# uZed_breakout.net
KiCad netlist of a schematic drawn in Altium Designer
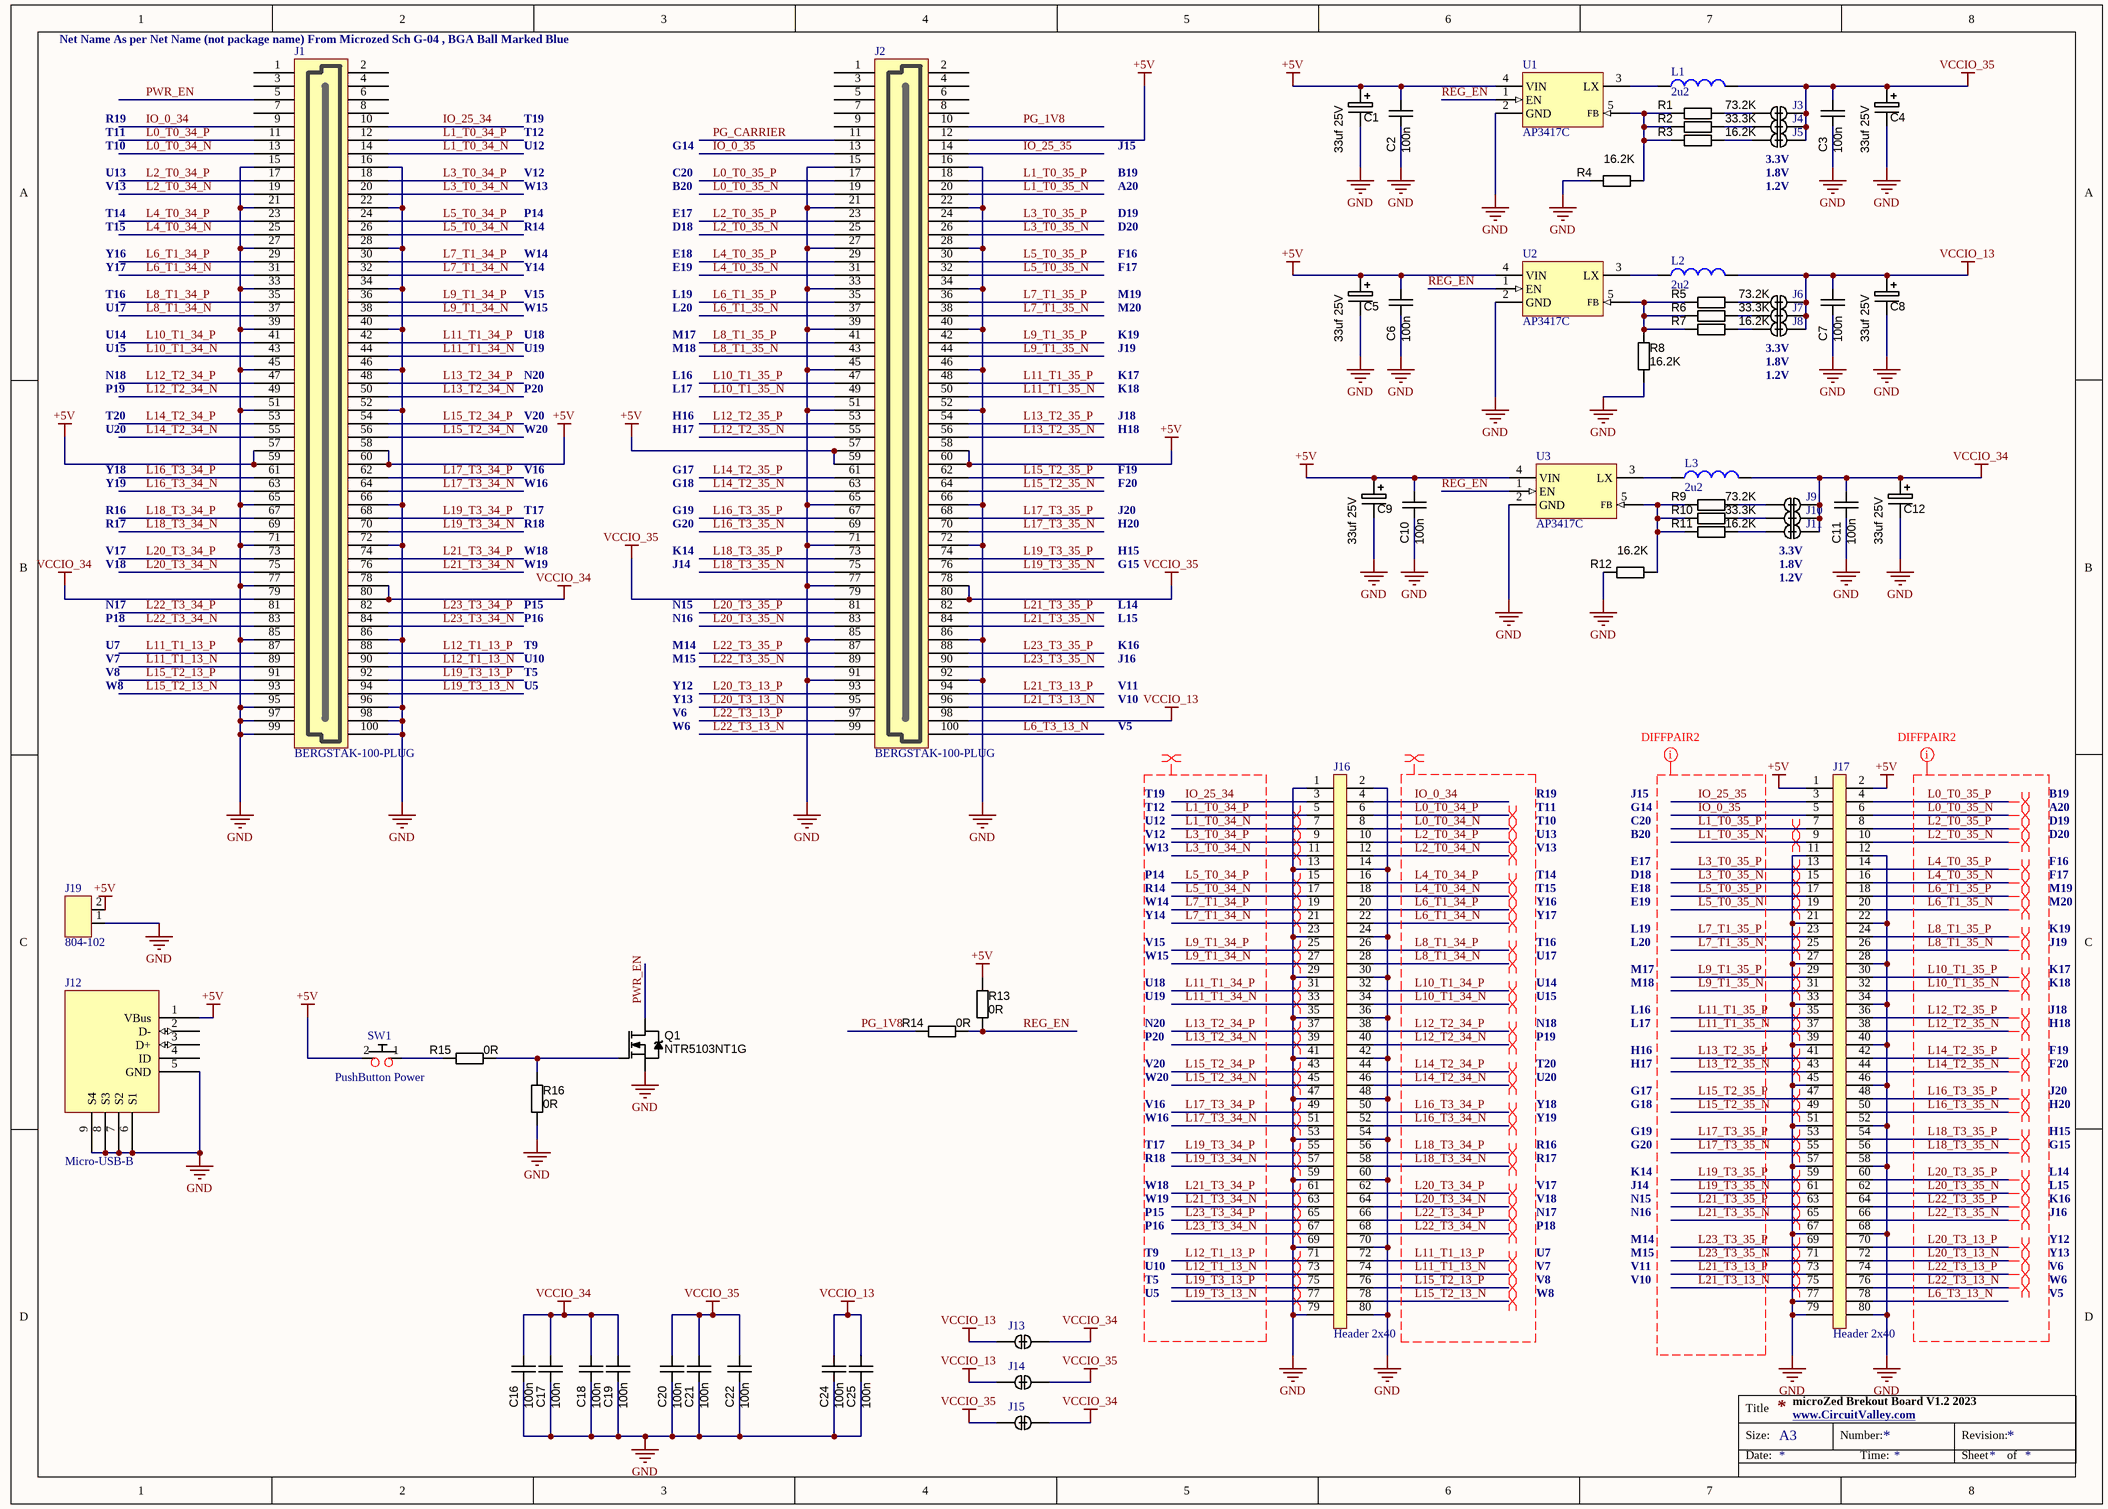
[diagram p0: uZed_breakout.SchDoc]

(export (version "E")
  (design (tool "Eeschema 10.0.6"))
  (components
    (comp (ref "C1")
      (value "33uf 25V")
      (footprint "CAPMP7343X310N")
      (description "Capacitor SMD Tant 330uF 20% 6V3 2917")
      (fields
        (field (name "TOLERANCE") "±20%")
        (field (name "MANUFACTURER PART NUMBER") "T520D337M006ATE015")
      )
      (libsource (lib "PBL - Capacitors") (part "CAPT_330u_2917_6V3"))
    )
    (comp (ref "C2")
      (value "100n")
      (footprint "CAPC1608N")
      (description "Capacitor SMD Cer 10pF 5% 50V NP0 0603")
      (fields (field (name "TOLERANCE") "±5%") (field (name "PART") "C0603X104K5RAC"))
      (libsource (lib "PBL - Capacitors") (part "CAPC_10p_0603_NP0_1%_50V"))
    )
    (comp (ref "C3")
      (value "100n")
      (footprint "CAPC1608N")
      (description "Capacitor SMD Cer 10pF 5% 50V NP0 0603")
      (fields (field (name "TOLERANCE") "±5%") (field (name "PART") "C0603X104K5RAC"))
      (libsource (lib "PBL - Capacitors") (part "CAPC_10p_0603_NP0_1%_50V"))
    )
    (comp (ref "C4")
      (value "33uf 25V")
      (footprint "CAPMP7343X310N")
      (description "Capacitor SMD Tant 330uF 20% 6V3 2917")
      (fields
        (field (name "TOLERANCE") "±20%")
        (field (name "MANUFACTURER PART NUMBER") "T520D337M006ATE015")
      )
      (libsource (lib "PBL - Capacitors") (part "CAPT_330u_2917_6V3"))
    )
    (comp (ref "C5")
      (value "33uf 25V")
      (footprint "CAPMP7343X310N")
      (description "Capacitor SMD Tant 330uF 20% 6V3 2917")
      (fields
        (field (name "TOLERANCE") "±20%")
        (field (name "MANUFACTURER PART NUMBER") "T520D337M006ATE015")
      )
      (libsource (lib "PBL - Capacitors") (part "CAPT_330u_2917_6V3"))
    )
    (comp (ref "C6")
      (value "100n")
      (footprint "CAPC1608N")
      (description "Capacitor SMD Cer 10pF 5% 50V NP0 0603")
      (fields (field (name "TOLERANCE") "±5%") (field (name "PART") "C0603X104K5RAC"))
      (libsource (lib "PBL - Capacitors") (part "CAPC_10p_0603_NP0_1%_50V"))
    )
    (comp (ref "C7")
      (value "100n")
      (footprint "CAPC1608N")
      (description "Capacitor SMD Cer 10pF 5% 50V NP0 0603")
      (fields (field (name "TOLERANCE") "±5%") (field (name "PART") "C0603X104K5RAC"))
      (libsource (lib "PBL - Capacitors") (part "CAPC_10p_0603_NP0_1%_50V"))
    )
    (comp (ref "C8")
      (value "33uf 25V")
      (footprint "CAPMP7343X310N")
      (description "Capacitor SMD Tant 330uF 20% 6V3 2917")
      (fields
        (field (name "TOLERANCE") "±20%")
        (field (name "MANUFACTURER PART NUMBER") "T520D337M006ATE015")
      )
      (libsource (lib "PBL - Capacitors") (part "CAPT_330u_2917_6V3"))
    )
    (comp (ref "C9")
      (value "33uf 25V")
      (footprint "CAPMP7343X310N")
      (description "Capacitor SMD Tant 330uF 20% 6V3 2917")
      (fields
        (field (name "TOLERANCE") "±20%")
        (field (name "MANUFACTURER PART NUMBER") "T520D337M006ATE015")
      )
      (libsource (lib "PBL - Capacitors") (part "CAPT_330u_2917_6V3"))
    )
    (comp (ref "C10")
      (value "100n")
      (footprint "CAPC1608N")
      (description "Capacitor SMD Cer 10pF 5% 50V NP0 0603")
      (fields (field (name "TOLERANCE") "±5%") (field (name "PART") "C0603X104K5RAC"))
      (libsource (lib "PBL - Capacitors") (part "CAPC_10p_0603_NP0_1%_50V"))
    )
    (comp (ref "C11")
      (value "100n")
      (footprint "CAPC1608N")
      (description "Capacitor SMD Cer 10pF 5% 50V NP0 0603")
      (fields (field (name "TOLERANCE") "±5%") (field (name "PART") "C0603X104K5RAC"))
      (libsource (lib "PBL - Capacitors") (part "CAPC_10p_0603_NP0_1%_50V"))
    )
    (comp (ref "C12")
      (value "33uf 25V")
      (footprint "CAPMP7343X310N")
      (description "Capacitor SMD Tant 330uF 20% 6V3 2917")
      (fields
        (field (name "TOLERANCE") "±20%")
        (field (name "MANUFACTURER PART NUMBER") "T520D337M006ATE015")
      )
      (libsource (lib "PBL - Capacitors") (part "CAPT_330u_2917_6V3"))
    )
    (comp (ref "C16")
      (value "100n")
      (footprint "CAPC1608N")
      (description "Capacitor SMD Cer 10pF 5% 50V NP0 0603")
      (fields (field (name "TOLERANCE") "±5%") (field (name "PART") "C0603X104K5RAC"))
      (libsource (lib "PBL - Capacitors") (part "CAPC_10p_0603_NP0_1%_50V"))
    )
    (comp (ref "C17")
      (value "100n")
      (footprint "CAPC1608N")
      (description "Capacitor SMD Cer 10pF 5% 50V NP0 0603")
      (fields (field (name "TOLERANCE") "±5%") (field (name "PART") "C0603X104K5RAC"))
      (libsource (lib "PBL - Capacitors") (part "CAPC_10p_0603_NP0_1%_50V"))
    )
    (comp (ref "C18")
      (value "100n")
      (footprint "CAPC1608N")
      (description "Capacitor SMD Cer 10pF 5% 50V NP0 0603")
      (fields (field (name "TOLERANCE") "±5%") (field (name "PART") "C0603X104K5RAC"))
      (libsource (lib "PBL - Capacitors") (part "CAPC_10p_0603_NP0_1%_50V"))
    )
    (comp (ref "C19")
      (value "100n")
      (footprint "CAPC1608N")
      (description "Capacitor SMD Cer 10pF 5% 50V NP0 0603")
      (fields (field (name "TOLERANCE") "±5%") (field (name "PART") "C0603X104K5RAC"))
      (libsource (lib "PBL - Capacitors") (part "CAPC_10p_0603_NP0_1%_50V"))
    )
    (comp (ref "C20")
      (value "100n")
      (footprint "CAPC1608N")
      (description "Capacitor SMD Cer 10pF 5% 50V NP0 0603")
      (fields (field (name "TOLERANCE") "±5%") (field (name "PART") "C0603X104K5RAC"))
      (libsource (lib "PBL - Capacitors") (part "CAPC_10p_0603_NP0_1%_50V"))
    )
    (comp (ref "C21")
      (value "100n")
      (footprint "CAPC1608N")
      (description "Capacitor SMD Cer 10pF 5% 50V NP0 0603")
      (fields (field (name "TOLERANCE") "±5%") (field (name "PART") "C0603X104K5RAC"))
      (libsource (lib "PBL - Capacitors") (part "CAPC_10p_0603_NP0_1%_50V"))
    )
    (comp (ref "C22")
      (value "100n")
      (footprint "CAPC1608N")
      (description "Capacitor SMD Cer 10pF 5% 50V NP0 0603")
      (fields (field (name "TOLERANCE") "±5%") (field (name "PART") "C0603X104K5RAC"))
      (libsource (lib "PBL - Capacitors") (part "CAPC_10p_0603_NP0_1%_50V"))
    )
    (comp (ref "C24")
      (value "100n")
      (footprint "CAPC1608N")
      (description "Capacitor SMD Cer 10pF 5% 50V NP0 0603")
      (fields (field (name "TOLERANCE") "±5%") (field (name "PART") "C0603X104K5RAC"))
      (libsource (lib "PBL - Capacitors") (part "CAPC_10p_0603_NP0_1%_50V"))
    )
    (comp (ref "C25")
      (value "100n")
      (footprint "CAPC1608N")
      (description "Capacitor SMD Cer 10pF 5% 50V NP0 0603")
      (fields (field (name "TOLERANCE") "±5%") (field (name "PART") "C0603X104K5RAC"))
      (libsource (lib "PBL - Capacitors") (part "CAPC_10p_0603_NP0_1%_50V"))
    )
    (comp (ref "J1")
      (value "BERGSTAK-100-PLUG")
      (footprint "61083-101400LF")
      (libsource (lib "cvlib") (part "BERGSTAK-100-PLUG"))
    )
    (comp (ref "J2")
      (value "BERGSTAK-100-PLUG")
      (footprint "61083-101400LF")
      (libsource (lib "cvlib") (part "BERGSTAK-100-PLUG"))
    )
    (comp (ref "J3")
      (value "~")
      (footprint "BYPASS-CLOSED")
      (description "SOLDERDOT BYPASS")
      (libsource (lib "Generic") (part "BYPASS-CLOSED"))
    )
    (comp (ref "J4")
      (value "~")
      (footprint "BYPASS-CLOSED")
      (description "SOLDERDOT BYPASS")
      (libsource (lib "Generic") (part "BYPASS-CLOSED"))
    )
    (comp (ref "J5")
      (value "~")
      (footprint "BYPASS-CLOSED")
      (description "SOLDERDOT BYPASS")
      (libsource (lib "Generic") (part "BYPASS-CLOSED"))
    )
    (comp (ref "J6")
      (value "~")
      (footprint "BYPASS-CLOSED")
      (description "SOLDERDOT BYPASS")
      (libsource (lib "Generic") (part "BYPASS-CLOSED"))
    )
    (comp (ref "J7")
      (value "~")
      (footprint "BYPASS-CLOSED")
      (description "SOLDERDOT BYPASS")
      (libsource (lib "Generic") (part "BYPASS-CLOSED"))
    )
    (comp (ref "J8")
      (value "~")
      (footprint "BYPASS-CLOSED")
      (description "SOLDERDOT BYPASS")
      (libsource (lib "Generic") (part "BYPASS-CLOSED"))
    )
    (comp (ref "J9")
      (value "~")
      (footprint "BYPASS-CLOSED")
      (description "SOLDERDOT BYPASS")
      (libsource (lib "Generic") (part "BYPASS-CLOSED"))
    )
    (comp (ref "J10")
      (value "~")
      (footprint "BYPASS-CLOSED")
      (description "SOLDERDOT BYPASS")
      (libsource (lib "Generic") (part "BYPASS-CLOSED"))
    )
    (comp (ref "J11")
      (value "~")
      (footprint "BYPASS-CLOSED")
      (description "SOLDERDOT BYPASS")
      (libsource (lib "Generic") (part "BYPASS-CLOSED"))
    )
    (comp (ref "J12")
      (value "Micro-USB-B")
      (footprint "10118193-0001lfc")
      (fields (field (name "PART") "10118193-0001lfc"))
      (libsource (lib "USB-MICROB-HW-MC-5F") (part "Micro-USB-B"))
    )
    (comp (ref "J13")
      (value "~")
      (footprint "BYPASS-CLOSED")
      (description "SOLDERDOT BYPASS")
      (libsource (lib "Generic") (part "BYPASS-CLOSED"))
    )
    (comp (ref "J14")
      (value "~")
      (footprint "BYPASS-CLOSED")
      (description "SOLDERDOT BYPASS")
      (libsource (lib "Generic") (part "BYPASS-CLOSED"))
    )
    (comp (ref "J15")
      (value "~")
      (footprint "BYPASS-CLOSED")
      (description "SOLDERDOT BYPASS")
      (libsource (lib "Generic") (part "BYPASS-CLOSED"))
    )
    (comp (ref "J16")
      (value "Header 2x40")
      (footprint "Header_2x40")
      (libsource (lib "cvlib") (part "Header_2x40"))
    )
    (comp (ref "J17")
      (value "Header 2x40")
      (footprint "Header_2x40")
      (libsource (lib "cvlib") (part "Header_2x40"))
    )
    (comp (ref "J19") (value "804-102") (footprint "804-102") (libsource (lib "cvlib") (part "804-102")))
    (comp (ref "L1")
      (value "2u2")
      (footprint "TAIYO_NRS4018T2R2MDGJ")
      (fields (field (name "PARTNUMBER") "NRS4018T2R2MDGJ"))
      (libsource (lib "Inductor") (part "inductor_smd"))
    )
    (comp (ref "L2")
      (value "2u2")
      (footprint "TAIYO_NRS4018T2R2MDGJ")
      (fields (field (name "PARTNUMBER") "NRS4018T2R2MDGJ"))
      (libsource (lib "Inductor") (part "inductor_smd"))
    )
    (comp (ref "L3")
      (value "2u2")
      (footprint "TAIYO_NRS4018T2R2MDGJ")
      (fields (field (name "PARTNUMBER") "NRS4018T2R2MDGJ"))
      (libsource (lib "Inductor") (part "inductor_smd"))
    )
    (comp (ref "Q1")
      (value "NTR5103NT1G")
      (footprint "SOT23-3")
      (description "MOSFET SMD N-CH 100V 170mA SOT23-3")
      (libsource (lib "PBL - Transistors") (part "MOSFET_BSS123"))
    )
    (comp (ref "R1")
      (value "73.2K")
      (footprint "RESC1608N_ZERO")
      (description "Resistor SMD chip 0.0 Ohm 0.1W 0603")
      (fields (field (name "TOLERANCE") "±5%") (field (name "Comment") "Thick Film"))
      (libsource (lib "PBL - Resistors") (part "RES_0R_0603"))
    )
    (comp (ref "R2")
      (value "33.3K")
      (footprint "RESC1608N_ZERO")
      (description "Resistor SMD chip 0.0 Ohm 0.1W 0603")
      (fields (field (name "TOLERANCE") "±5%") (field (name "Comment") "Thick Film"))
      (libsource (lib "PBL - Resistors") (part "RES_0R_0603"))
    )
    (comp (ref "R3")
      (value "16.2K")
      (footprint "RESC1608N_ZERO")
      (description "Resistor SMD chip 0.0 Ohm 0.1W 0603")
      (fields (field (name "TOLERANCE") "±5%") (field (name "Comment") "Thick Film"))
      (libsource (lib "PBL - Resistors") (part "RES_0R_0603"))
    )
    (comp (ref "R4")
      (value "16.2K")
      (footprint "RESC1608N_ZERO")
      (description "Resistor SMD chip 0.0 Ohm 0.1W 0603")
      (fields (field (name "TOLERANCE") "±5%") (field (name "Comment") "Thick Film"))
      (libsource (lib "PBL - Resistors") (part "RES_0R_0603"))
    )
    (comp (ref "R5")
      (value "73.2K")
      (footprint "RESC1608N_ZERO")
      (description "Resistor SMD chip 0.0 Ohm 0.1W 0603")
      (fields (field (name "TOLERANCE") "±5%") (field (name "Comment") "Thick Film"))
      (libsource (lib "") (part "RES_0R_0603_2"))
    )
    (comp (ref "R6")
      (value "33.3K")
      (footprint "RESC1608N_ZERO")
      (description "Resistor SMD chip 0.0 Ohm 0.1W 0603")
      (fields (field (name "TOLERANCE") "±5%") (field (name "Comment") "Thick Film"))
      (libsource (lib "") (part "RES_0R_0603_2"))
    )
    (comp (ref "R7")
      (value "16.2K")
      (footprint "RESC1608N_ZERO")
      (description "Resistor SMD chip 0.0 Ohm 0.1W 0603")
      (fields (field (name "TOLERANCE") "±5%") (field (name "Comment") "Thick Film"))
      (libsource (lib "") (part "RES_0R_0603_2"))
    )
    (comp (ref "R8")
      (value "16.2K")
      (footprint "RESC1608N_ZERO")
      (description "Resistor SMD chip 0.0 Ohm 0.1W 0603")
      (fields (field (name "TOLERANCE") "±5%") (field (name "Comment") "Thick Film"))
      (libsource (lib "") (part "RES_0R_0603_3"))
    )
    (comp (ref "R9")
      (value "73.2K")
      (footprint "RESC1608N_ZERO")
      (description "Resistor SMD chip 0.0 Ohm 0.1W 0603")
      (fields (field (name "TOLERANCE") "±5%") (field (name "Comment") "Thick Film"))
      (libsource (lib "PBL - Resistors") (part "RES_0R_0603"))
    )
    (comp (ref "R10")
      (value "33.3K")
      (footprint "RESC1608N_ZERO")
      (description "Resistor SMD chip 0.0 Ohm 0.1W 0603")
      (fields (field (name "TOLERANCE") "±5%") (field (name "Comment") "Thick Film"))
      (libsource (lib "PBL - Resistors") (part "RES_0R_0603"))
    )
    (comp (ref "R11")
      (value "16.2K")
      (footprint "RESC1608N_ZERO")
      (description "Resistor SMD chip 0.0 Ohm 0.1W 0603")
      (fields (field (name "TOLERANCE") "±5%") (field (name "Comment") "Thick Film"))
      (libsource (lib "PBL - Resistors") (part "RES_0R_0603"))
    )
    (comp (ref "R12")
      (value "16.2K")
      (footprint "RESC1608N_ZERO")
      (description "Resistor SMD chip 0.0 Ohm 0.1W 0603")
      (fields (field (name "TOLERANCE") "±5%") (field (name "Comment") "Thick Film"))
      (libsource (lib "PBL - Resistors") (part "RES_0R_0603"))
    )
    (comp (ref "R13")
      (value "0R")
      (footprint "RESC1608N_ZERO")
      (description "Resistor SMD chip 0.0 Ohm 0.1W 0603")
      (fields (field (name "TOLERANCE") "±5%") (field (name "Comment") "Thick Film"))
      (libsource (lib "") (part "RES_0R_0603_1"))
    )
    (comp (ref "R14")
      (value "0R")
      (footprint "RESC1608N_ZERO")
      (description "Resistor SMD chip 0.0 Ohm 0.1W 0603")
      (fields (field (name "TOLERANCE") "±5%") (field (name "Comment") "Thick Film"))
      (libsource (lib "PBL - Resistors") (part "RES_0R_0603"))
    )
    (comp (ref "R15")
      (value "0R")
      (footprint "RESC1608N_ZERO")
      (description "Resistor SMD chip 0.0 Ohm 0.1W 0603")
      (fields (field (name "TOLERANCE") "±5%") (field (name "Comment") "Thick Film"))
      (libsource (lib "PBL - Resistors") (part "RES_0R_0603"))
    )
    (comp (ref "R16")
      (value "0R")
      (footprint "RESC1608N_ZERO")
      (description "Resistor SMD chip 0.0 Ohm 0.1W 0603")
      (fields (field (name "TOLERANCE") "±5%") (field (name "Comment") "Thick Film"))
      (libsource (lib "") (part "RES_0R_0603_1"))
    )
    (comp (ref "SW1")
      (value "PushButton Power")
      (footprint "PushButtonGrid5.08x3.81")
      (libsource (lib "PushSwitchSmall") (part "PushButton"))
    )
    (comp (ref "U1") (value "AP3417C") (footprint "SOT23-5") (libsource (lib "cvlib") (part "AP3417C")))
    (comp (ref "U2") (value "AP3417C") (footprint "SOT23-5") (libsource (lib "cvlib") (part "AP3417C")))
    (comp (ref "U3") (value "AP3417C") (footprint "SOT23-5") (libsource (lib "cvlib") (part "AP3417C")))
  )
  (nets
    (net (code "1") (name "+5V") (class "Default")
      (node (ref "C1") (pin "1") (pintype "passive"))
      (node (ref "C10") (pin "2") (pintype "passive"))
      (node (ref "C2") (pin "2") (pintype "passive"))
      (node (ref "C5") (pin "1") (pintype "passive"))
      (node (ref "C6") (pin "2") (pintype "passive"))
      (node (ref "C9") (pin "1") (pintype "passive"))
      (node (ref "J1") (pin "57") (pinfunction "57_57") (pintype "passive"))
      (node (ref "J1") (pin "58") (pinfunction "58_58") (pintype "passive"))
      (node (ref "J1") (pin "59") (pinfunction "59_59") (pintype "passive"))
      (node (ref "J1") (pin "60") (pinfunction "60_60") (pintype "passive"))
      (node (ref "J12") (pin "1") (pinfunction "VBus_1") (pintype "power_in"))
      (node (ref "J17") (pin "1") (pinfunction "1_1") (pintype "passive"))
      (node (ref "J17") (pin "2") (pinfunction "2_2") (pintype "passive"))
      (node (ref "J19") (pin "2") (pinfunction "PW_2") (pintype "passive"))
      (node (ref "J2") (pin "12") (pinfunction "12_12") (pintype "passive"))
      (node (ref "J2") (pin "57") (pinfunction "57_57") (pintype "passive"))
      (node (ref "J2") (pin "58") (pinfunction "58_58") (pintype "passive"))
      (node (ref "J2") (pin "59") (pinfunction "59_59") (pintype "passive"))
      (node (ref "J2") (pin "60") (pinfunction "60_60") (pintype "passive"))
      (node (ref "R13") (pin "1") (pinfunction "1_1") (pintype "passive"))
      (node (ref "SW1") (pin "2") (pinfunction "P2_2") (pintype "passive"))
      (node (ref "U1") (pin "4") (pinfunction "VIN_4") (pintype "power_in"))
      (node (ref "U2") (pin "4") (pinfunction "VIN_4") (pintype "power_in"))
      (node (ref "U3") (pin "4") (pinfunction "VIN_4") (pintype "power_in"))
    )
    (net (code "3") (name "/IO_0_34") (class "Default")
      (node (ref "J1") (pin "9") (pinfunction "9_9") (pintype "passive"))
      (node (ref "J16") (pin "4") (pinfunction "4_4") (pintype "passive"))
    )
    (net (code "4") (name "/IO_0_35") (class "Default")
      (node (ref "J17") (pin "5") (pinfunction "5_5") (pintype "passive"))
      (node (ref "J2") (pin "13") (pinfunction "13_13") (pintype "passive"))
    )
    (net (code "5") (name "/IO_25_34") (class "Default")
      (node (ref "J1") (pin "10") (pinfunction "10_10") (pintype "passive"))
      (node (ref "J16") (pin "3") (pinfunction "3_3") (pintype "passive"))
    )
    (net (code "6") (name "/IO_25_35") (class "Default")
      (node (ref "J17") (pin "3") (pinfunction "3_3") (pintype "passive"))
      (node (ref "J2") (pin "14") (pinfunction "14_14") (pintype "passive"))
    )
    (net (code "7") (name "/L0_T0_34_N") (class "Default")
      (node (ref "J1") (pin "13") (pinfunction "13_13") (pintype "passive"))
      (node (ref "J16") (pin "8") (pinfunction "8_8") (pintype "passive"))
    )
    (net (code "8") (name "/L0_T0_34_P") (class "Default")
      (node (ref "J1") (pin "11") (pinfunction "11_11") (pintype "passive"))
      (node (ref "J16") (pin "6") (pinfunction "6_6") (pintype "passive"))
    )
    (net (code "9") (name "/L0_T0_35_N") (class "Default")
      (node (ref "J17") (pin "6") (pinfunction "6_6") (pintype "passive"))
      (node (ref "J2") (pin "19") (pinfunction "19_19") (pintype "passive"))
    )
    (net (code "10") (name "/L0_T0_35_P") (class "Default")
      (node (ref "J17") (pin "4") (pinfunction "4_4") (pintype "passive"))
      (node (ref "J2") (pin "17") (pinfunction "17_17") (pintype "passive"))
    )
    (net (code "11") (name "/L1_T0_34_N") (class "Default")
      (node (ref "J1") (pin "14") (pinfunction "14_14") (pintype "passive"))
      (node (ref "J16") (pin "7") (pinfunction "7_7") (pintype "passive"))
    )
    (net (code "12") (name "/L1_T0_34_P") (class "Default")
      (node (ref "J1") (pin "12") (pinfunction "12_12") (pintype "passive"))
      (node (ref "J16") (pin "5") (pinfunction "5_5") (pintype "passive"))
    )
    (net (code "13") (name "/L1_T0_35_N") (class "Default")
      (node (ref "J17") (pin "9") (pinfunction "9_9") (pintype "passive"))
      (node (ref "J2") (pin "20") (pinfunction "20_20") (pintype "passive"))
    )
    (net (code "14") (name "/L1_T0_35_P") (class "Default")
      (node (ref "J17") (pin "7") (pinfunction "7_7") (pintype "passive"))
      (node (ref "J2") (pin "18") (pinfunction "18_18") (pintype "passive"))
    )
    (net (code "15") (name "/L2_T0_34_N") (class "Default")
      (node (ref "J1") (pin "19") (pinfunction "19_19") (pintype "passive"))
      (node (ref "J16") (pin "12") (pinfunction "12_12") (pintype "passive"))
    )
    (net (code "16") (name "/L2_T0_34_P") (class "Default")
      (node (ref "J1") (pin "17") (pinfunction "17_17") (pintype "passive"))
      (node (ref "J16") (pin "10") (pinfunction "10_10") (pintype "passive"))
    )
    (net (code "17") (name "/L2_T0_35_N") (class "Default")
      (node (ref "J17") (pin "10") (pinfunction "10_10") (pintype "passive"))
      (node (ref "J2") (pin "25") (pinfunction "25_25") (pintype "passive"))
    )
    (net (code "18") (name "/L2_T0_35_P") (class "Default")
      (node (ref "J17") (pin "8") (pinfunction "8_8") (pintype "passive"))
      (node (ref "J2") (pin "23") (pinfunction "23_23") (pintype "passive"))
    )
    (net (code "19") (name "/L3_T0_34_N") (class "Default")
      (node (ref "J1") (pin "20") (pinfunction "20_20") (pintype "passive"))
      (node (ref "J16") (pin "11") (pinfunction "11_11") (pintype "passive"))
    )
    (net (code "20") (name "/L3_T0_34_P") (class "Default")
      (node (ref "J1") (pin "18") (pinfunction "18_18") (pintype "passive"))
      (node (ref "J16") (pin "9") (pinfunction "9_9") (pintype "passive"))
    )
    (net (code "21") (name "/L3_T0_35_N") (class "Default")
      (node (ref "J17") (pin "15") (pinfunction "15_15") (pintype "passive"))
      (node (ref "J2") (pin "26") (pinfunction "26_26") (pintype "passive"))
    )
    (net (code "22") (name "/L3_T0_35_P") (class "Default")
      (node (ref "J17") (pin "13") (pinfunction "13_13") (pintype "passive"))
      (node (ref "J2") (pin "24") (pinfunction "24_24") (pintype "passive"))
    )
    (net (code "23") (name "/L4_T0_34_N") (class "Default")
      (node (ref "J1") (pin "25") (pinfunction "25_25") (pintype "passive"))
      (node (ref "J16") (pin "18") (pinfunction "18_18") (pintype "passive"))
    )
    (net (code "24") (name "/L4_T0_34_P") (class "Default")
      (node (ref "J1") (pin "23") (pinfunction "23_23") (pintype "passive"))
      (node (ref "J16") (pin "16") (pinfunction "16_16") (pintype "passive"))
    )
    (net (code "25") (name "/L4_T0_35_N") (class "Default")
      (node (ref "J17") (pin "16") (pinfunction "16_16") (pintype "passive"))
      (node (ref "J2") (pin "31") (pinfunction "31_31") (pintype "passive"))
    )
    (net (code "26") (name "/L4_T0_35_P") (class "Default")
      (node (ref "J17") (pin "14") (pinfunction "14_14") (pintype "passive"))
      (node (ref "J2") (pin "29") (pinfunction "29_29") (pintype "passive"))
    )
    (net (code "27") (name "/L5_T0_34_N") (class "Default")
      (node (ref "J1") (pin "26") (pinfunction "26_26") (pintype "passive"))
      (node (ref "J16") (pin "17") (pinfunction "17_17") (pintype "passive"))
    )
    (net (code "28") (name "/L5_T0_34_P") (class "Default")
      (node (ref "J1") (pin "24") (pinfunction "24_24") (pintype "passive"))
      (node (ref "J16") (pin "15") (pinfunction "15_15") (pintype "passive"))
    )
    (net (code "29") (name "/L5_T0_35_N") (class "Default")
      (node (ref "J17") (pin "19") (pinfunction "19_19") (pintype "passive"))
      (node (ref "J2") (pin "32") (pinfunction "32_32") (pintype "passive"))
    )
    (net (code "30") (name "/L5_T0_35_P") (class "Default")
      (node (ref "J17") (pin "17") (pinfunction "17_17") (pintype "passive"))
      (node (ref "J2") (pin "30") (pinfunction "30_30") (pintype "passive"))
    )
    (net (code "31") (name "/L6_T1_34_N") (class "Default")
      (node (ref "J1") (pin "31") (pinfunction "31_31") (pintype "passive"))
      (node (ref "J16") (pin "22") (pinfunction "22_22") (pintype "passive"))
    )
    (net (code "32") (name "/L6_T1_34_P") (class "Default")
      (node (ref "J1") (pin "29") (pinfunction "29_29") (pintype "passive"))
      (node (ref "J16") (pin "20") (pinfunction "20_20") (pintype "passive"))
    )
    (net (code "33") (name "/L6_T1_35_N") (class "Default")
      (node (ref "J17") (pin "20") (pinfunction "20_20") (pintype "passive"))
      (node (ref "J2") (pin "37") (pinfunction "37_37") (pintype "passive"))
    )
    (net (code "34") (name "/L6_T1_35_P") (class "Default")
      (node (ref "J17") (pin "18") (pinfunction "18_18") (pintype "passive"))
      (node (ref "J2") (pin "35") (pinfunction "35_35") (pintype "passive"))
    )
    (net (code "35") (name "/L6_T3_13_N") (class "Default")
      (node (ref "J17") (pin "78") (pinfunction "78_78") (pintype "passive"))
      (node (ref "J2") (pin "100") (pinfunction "100_100") (pintype "passive"))
    )
    (net (code "36") (name "/L7_T1_34_N") (class "Default")
      (node (ref "J1") (pin "32") (pinfunction "32_32") (pintype "passive"))
      (node (ref "J16") (pin "21") (pinfunction "21_21") (pintype "passive"))
    )
    (net (code "37") (name "/L7_T1_34_P") (class "Default")
      (node (ref "J1") (pin "30") (pinfunction "30_30") (pintype "passive"))
      (node (ref "J16") (pin "19") (pinfunction "19_19") (pintype "passive"))
    )
    (net (code "38") (name "/L7_T1_35_N") (class "Default")
      (node (ref "J17") (pin "25") (pinfunction "25_25") (pintype "passive"))
      (node (ref "J2") (pin "38") (pinfunction "38_38") (pintype "passive"))
    )
    (net (code "39") (name "/L7_T1_35_P") (class "Default")
      (node (ref "J17") (pin "23") (pinfunction "23_23") (pintype "passive"))
      (node (ref "J2") (pin "36") (pinfunction "36_36") (pintype "passive"))
    )
    (net (code "40") (name "/L8_T1_34_N") (class "Default")
      (node (ref "J1") (pin "37") (pinfunction "37_37") (pintype "passive"))
      (node (ref "J16") (pin "28") (pinfunction "28_28") (pintype "passive"))
    )
    (net (code "41") (name "/L8_T1_34_P") (class "Default")
      (node (ref "J1") (pin "35") (pinfunction "35_35") (pintype "passive"))
      (node (ref "J16") (pin "26") (pinfunction "26_26") (pintype "passive"))
    )
    (net (code "42") (name "/L8_T1_35_N") (class "Default")
      (node (ref "J17") (pin "26") (pinfunction "26_26") (pintype "passive"))
      (node (ref "J2") (pin "43") (pinfunction "43_43") (pintype "passive"))
    )
    (net (code "43") (name "/L8_T1_35_P") (class "Default")
      (node (ref "J17") (pin "24") (pinfunction "24_24") (pintype "passive"))
      (node (ref "J2") (pin "41") (pinfunction "41_41") (pintype "passive"))
    )
    (net (code "44") (name "/L9_T1_34_N") (class "Default")
      (node (ref "J1") (pin "38") (pinfunction "38_38") (pintype "passive"))
      (node (ref "J16") (pin "27") (pinfunction "27_27") (pintype "passive"))
    )
    (net (code "45") (name "/L9_T1_34_P") (class "Default")
      (node (ref "J1") (pin "36") (pinfunction "36_36") (pintype "passive"))
      (node (ref "J16") (pin "25") (pinfunction "25_25") (pintype "passive"))
    )
    (net (code "46") (name "/L9_T1_35_N") (class "Default")
      (node (ref "J17") (pin "31") (pinfunction "31_31") (pintype "passive"))
      (node (ref "J2") (pin "44") (pinfunction "44_44") (pintype "passive"))
    )
    (net (code "47") (name "/L9_T1_35_P") (class "Default")
      (node (ref "J17") (pin "29") (pinfunction "29_29") (pintype "passive"))
      (node (ref "J2") (pin "42") (pinfunction "42_42") (pintype "passive"))
    )
    (net (code "48") (name "/L10_T1_34_N") (class "Default")
      (node (ref "J1") (pin "43") (pinfunction "43_43") (pintype "passive"))
      (node (ref "J16") (pin "34") (pinfunction "34_34") (pintype "passive"))
    )
    (net (code "49") (name "/L10_T1_34_P") (class "Default")
      (node (ref "J1") (pin "41") (pinfunction "41_41") (pintype "passive"))
      (node (ref "J16") (pin "32") (pinfunction "32_32") (pintype "passive"))
    )
    (net (code "50") (name "/L10_T1_35_N") (class "Default")
      (node (ref "J17") (pin "32") (pinfunction "32_32") (pintype "passive"))
      (node (ref "J2") (pin "49") (pinfunction "49_49") (pintype "passive"))
    )
    (net (code "51") (name "/L10_T1_35_P") (class "Default")
      (node (ref "J17") (pin "30") (pinfunction "30_30") (pintype "passive"))
      (node (ref "J2") (pin "47") (pinfunction "47_47") (pintype "passive"))
    )
    (net (code "52") (name "/L11_T1_13_N") (class "Default")
      (node (ref "J1") (pin "89") (pinfunction "89_89") (pintype "passive"))
      (node (ref "J16") (pin "74") (pinfunction "74_74") (pintype "passive"))
    )
    (net (code "53") (name "/L11_T1_13_P") (class "Default")
      (node (ref "J1") (pin "87") (pinfunction "87_87") (pintype "passive"))
      (node (ref "J16") (pin "72") (pinfunction "72_72") (pintype "passive"))
    )
    (net (code "54") (name "/L11_T1_34_N") (class "Default")
      (node (ref "J1") (pin "44") (pinfunction "44_44") (pintype "passive"))
      (node (ref "J16") (pin "33") (pinfunction "33_33") (pintype "passive"))
    )
    (net (code "55") (name "/L11_T1_34_P") (class "Default")
      (node (ref "J1") (pin "42") (pinfunction "42_42") (pintype "passive"))
      (node (ref "J16") (pin "31") (pinfunction "31_31") (pintype "passive"))
    )
    (net (code "56") (name "/L11_T1_35_N") (class "Default")
      (node (ref "J17") (pin "37") (pinfunction "37_37") (pintype "passive"))
      (node (ref "J2") (pin "50") (pinfunction "50_50") (pintype "passive"))
    )
    (net (code "57") (name "/L11_T1_35_P") (class "Default")
      (node (ref "J17") (pin "35") (pinfunction "35_35") (pintype "passive"))
      (node (ref "J2") (pin "48") (pinfunction "48_48") (pintype "passive"))
    )
    (net (code "58") (name "/L12_T1_13_N") (class "Default")
      (node (ref "J1") (pin "90") (pinfunction "90_90") (pintype "passive"))
      (node (ref "J16") (pin "73") (pinfunction "73_73") (pintype "passive"))
    )
    (net (code "59") (name "/L12_T1_13_P") (class "Default")
      (node (ref "J1") (pin "88") (pinfunction "88_88") (pintype "passive"))
      (node (ref "J16") (pin "71") (pinfunction "71_71") (pintype "passive"))
    )
    (net (code "60") (name "/L12_T2_34_N") (class "Default")
      (node (ref "J1") (pin "49") (pinfunction "49_49") (pintype "passive"))
      (node (ref "J16") (pin "40") (pinfunction "40_40") (pintype "passive"))
    )
    (net (code "61") (name "/L12_T2_34_P") (class "Default")
      (node (ref "J1") (pin "47") (pinfunction "47_47") (pintype "passive"))
      (node (ref "J16") (pin "38") (pinfunction "38_38") (pintype "passive"))
    )
    (net (code "62") (name "/L12_T2_35_N") (class "Default")
      (node (ref "J17") (pin "38") (pinfunction "38_38") (pintype "passive"))
      (node (ref "J2") (pin "55") (pinfunction "55_55") (pintype "passive"))
    )
    (net (code "63") (name "/L12_T2_35_P") (class "Default")
      (node (ref "J17") (pin "36") (pinfunction "36_36") (pintype "passive"))
      (node (ref "J2") (pin "53") (pinfunction "53_53") (pintype "passive"))
    )
    (net (code "64") (name "/L13_T2_34_N") (class "Default")
      (node (ref "J1") (pin "50") (pinfunction "50_50") (pintype "passive"))
      (node (ref "J16") (pin "39") (pinfunction "39_39") (pintype "passive"))
    )
    (net (code "65") (name "/L13_T2_34_P") (class "Default")
      (node (ref "J1") (pin "48") (pinfunction "48_48") (pintype "passive"))
      (node (ref "J16") (pin "37") (pinfunction "37_37") (pintype "passive"))
    )
    (net (code "66") (name "/L13_T2_35_N") (class "Default")
      (node (ref "J17") (pin "43") (pinfunction "43_43") (pintype "passive"))
      (node (ref "J2") (pin "56") (pinfunction "56_56") (pintype "passive"))
    )
    (net (code "67") (name "/L13_T2_35_P") (class "Default")
      (node (ref "J17") (pin "41") (pinfunction "41_41") (pintype "passive"))
      (node (ref "J2") (pin "54") (pinfunction "54_54") (pintype "passive"))
    )
    (net (code "68") (name "/L14_T2_34_N") (class "Default")
      (node (ref "J1") (pin "55") (pinfunction "55_55") (pintype "passive"))
      (node (ref "J16") (pin "46") (pinfunction "46_46") (pintype "passive"))
    )
    (net (code "69") (name "/L14_T2_34_P") (class "Default")
      (node (ref "J1") (pin "53") (pinfunction "53_53") (pintype "passive"))
      (node (ref "J16") (pin "44") (pinfunction "44_44") (pintype "passive"))
    )
    (net (code "70") (name "/L14_T2_35_N") (class "Default")
      (node (ref "J17") (pin "44") (pinfunction "44_44") (pintype "passive"))
      (node (ref "J2") (pin "63") (pinfunction "63_63") (pintype "passive"))
    )
    (net (code "71") (name "/L14_T2_35_P") (class "Default")
      (node (ref "J17") (pin "42") (pinfunction "42_42") (pintype "passive"))
      (node (ref "J2") (pin "61") (pinfunction "61_61") (pintype "passive"))
    )
    (net (code "72") (name "/L15_T2_13_N") (class "Default")
      (node (ref "J1") (pin "93") (pinfunction "93_93") (pintype "passive"))
      (node (ref "J16") (pin "78") (pinfunction "78_78") (pintype "passive"))
    )
    (net (code "73") (name "/L15_T2_13_P") (class "Default")
      (node (ref "J1") (pin "91") (pinfunction "91_91") (pintype "passive"))
      (node (ref "J16") (pin "76") (pinfunction "76_76") (pintype "passive"))
    )
    (net (code "74") (name "/L15_T2_34_N") (class "Default")
      (node (ref "J1") (pin "56") (pinfunction "56_56") (pintype "passive"))
      (node (ref "J16") (pin "45") (pinfunction "45_45") (pintype "passive"))
    )
    (net (code "75") (name "/L15_T2_34_P") (class "Default")
      (node (ref "J1") (pin "54") (pinfunction "54_54") (pintype "passive"))
      (node (ref "J16") (pin "43") (pinfunction "43_43") (pintype "passive"))
    )
    (net (code "76") (name "/L15_T2_35_N") (class "Default")
      (node (ref "J17") (pin "49") (pinfunction "49_49") (pintype "passive"))
      (node (ref "J2") (pin "64") (pinfunction "64_64") (pintype "passive"))
    )
    (net (code "77") (name "/L15_T2_35_P") (class "Default")
      (node (ref "J17") (pin "47") (pinfunction "47_47") (pintype "passive"))
      (node (ref "J2") (pin "62") (pinfunction "62_62") (pintype "passive"))
    )
    (net (code "78") (name "/L16_T3_34_N") (class "Default")
      (node (ref "J1") (pin "63") (pinfunction "63_63") (pintype "passive"))
      (node (ref "J16") (pin "52") (pinfunction "52_52") (pintype "passive"))
    )
    (net (code "79") (name "/L16_T3_34_P") (class "Default")
      (node (ref "J1") (pin "61") (pinfunction "61_61") (pintype "passive"))
      (node (ref "J16") (pin "50") (pinfunction "50_50") (pintype "passive"))
    )
    (net (code "80") (name "/L16_T3_35_N") (class "Default")
      (node (ref "J17") (pin "50") (pinfunction "50_50") (pintype "passive"))
      (node (ref "J2") (pin "69") (pinfunction "69_69") (pintype "passive"))
    )
    (net (code "81") (name "/L16_T3_35_P") (class "Default")
      (node (ref "J17") (pin "48") (pinfunction "48_48") (pintype "passive"))
      (node (ref "J2") (pin "67") (pinfunction "67_67") (pintype "passive"))
    )
    (net (code "82") (name "/L17_T3_34_N") (class "Default")
      (node (ref "J1") (pin "64") (pinfunction "64_64") (pintype "passive"))
      (node (ref "J16") (pin "51") (pinfunction "51_51") (pintype "passive"))
    )
    (net (code "83") (name "/L17_T3_34_P") (class "Default")
      (node (ref "J1") (pin "62") (pinfunction "62_62") (pintype "passive"))
      (node (ref "J16") (pin "49") (pinfunction "49_49") (pintype "passive"))
    )
    (net (code "84") (name "/L17_T3_35_N") (class "Default")
      (node (ref "J17") (pin "55") (pinfunction "55_55") (pintype "passive"))
      (node (ref "J2") (pin "70") (pinfunction "70_70") (pintype "passive"))
    )
    (net (code "85") (name "/L17_T3_35_P") (class "Default")
      (node (ref "J17") (pin "53") (pinfunction "53_53") (pintype "passive"))
      (node (ref "J2") (pin "68") (pinfunction "68_68") (pintype "passive"))
    )
    (net (code "86") (name "/L18_T3_34_N") (class "Default")
      (node (ref "J1") (pin "69") (pinfunction "69_69") (pintype "passive"))
      (node (ref "J16") (pin "58") (pinfunction "58_58") (pintype "passive"))
    )
    (net (code "87") (name "/L18_T3_34_P") (class "Default")
      (node (ref "J1") (pin "67") (pinfunction "67_67") (pintype "passive"))
      (node (ref "J16") (pin "56") (pinfunction "56_56") (pintype "passive"))
    )
    (net (code "88") (name "/L18_T3_35_N") (class "Default")
      (node (ref "J17") (pin "56") (pinfunction "56_56") (pintype "passive"))
      (node (ref "J2") (pin "75") (pinfunction "75_75") (pintype "passive"))
    )
    (net (code "89") (name "/L18_T3_35_P") (class "Default")
      (node (ref "J17") (pin "54") (pinfunction "54_54") (pintype "passive"))
      (node (ref "J2") (pin "73") (pinfunction "73_73") (pintype "passive"))
    )
    (net (code "90") (name "/L19_T3_13_N") (class "Default")
      (node (ref "J1") (pin "94") (pinfunction "94_94") (pintype "passive"))
      (node (ref "J16") (pin "77") (pinfunction "77_77") (pintype "passive"))
    )
    (net (code "91") (name "/L19_T3_13_P") (class "Default")
      (node (ref "J1") (pin "92") (pinfunction "92_92") (pintype "passive"))
      (node (ref "J16") (pin "75") (pinfunction "75_75") (pintype "passive"))
    )
    (net (code "92") (name "/L19_T3_34_N") (class "Default")
      (node (ref "J1") (pin "70") (pinfunction "70_70") (pintype "passive"))
      (node (ref "J16") (pin "57") (pinfunction "57_57") (pintype "passive"))
    )
    (net (code "93") (name "/L19_T3_34_P") (class "Default")
      (node (ref "J1") (pin "68") (pinfunction "68_68") (pintype "passive"))
      (node (ref "J16") (pin "55") (pinfunction "55_55") (pintype "passive"))
    )
    (net (code "94") (name "/L19_T3_35_N") (class "Default")
      (node (ref "J17") (pin "61") (pinfunction "61_61") (pintype "passive"))
      (node (ref "J2") (pin "76") (pinfunction "76_76") (pintype "passive"))
    )
    (net (code "95") (name "/L19_T3_35_P") (class "Default")
      (node (ref "J17") (pin "59") (pinfunction "59_59") (pintype "passive"))
      (node (ref "J2") (pin "74") (pinfunction "74_74") (pintype "passive"))
    )
    (net (code "96") (name "/L20_T3_13_N") (class "Default")
      (node (ref "J17") (pin "72") (pinfunction "72_72") (pintype "passive"))
      (node (ref "J2") (pin "95") (pinfunction "95_95") (pintype "passive"))
    )
    (net (code "97") (name "/L20_T3_13_P") (class "Default")
      (node (ref "J17") (pin "70") (pinfunction "70_70") (pintype "passive"))
      (node (ref "J2") (pin "93") (pinfunction "93_93") (pintype "passive"))
    )
    (net (code "98") (name "/L20_T3_34_N") (class "Default")
      (node (ref "J1") (pin "75") (pinfunction "75_75") (pintype "passive"))
      (node (ref "J16") (pin "64") (pinfunction "64_64") (pintype "passive"))
    )
    (net (code "99") (name "/L20_T3_34_P") (class "Default")
      (node (ref "J1") (pin "73") (pinfunction "73_73") (pintype "passive"))
      (node (ref "J16") (pin "62") (pinfunction "62_62") (pintype "passive"))
    )
    (net (code "100") (name "/L20_T3_35_N") (class "Default")
      (node (ref "J17") (pin "62") (pinfunction "62_62") (pintype "passive"))
      (node (ref "J2") (pin "83") (pinfunction "83_83") (pintype "passive"))
    )
    (net (code "101") (name "/L20_T3_35_P") (class "Default")
      (node (ref "J17") (pin "60") (pinfunction "60_60") (pintype "passive"))
      (node (ref "J2") (pin "81") (pinfunction "81_81") (pintype "passive"))
    )
    (net (code "102") (name "/L21_T3_13_N") (class "Default")
      (node (ref "J17") (pin "75") (pinfunction "75_75") (pintype "passive"))
      (node (ref "J2") (pin "96") (pinfunction "96_96") (pintype "passive"))
    )
    (net (code "103") (name "/L21_T3_13_P") (class "Default")
      (node (ref "J17") (pin "73") (pinfunction "73_73") (pintype "passive"))
      (node (ref "J2") (pin "94") (pinfunction "94_94") (pintype "passive"))
    )
    (net (code "104") (name "/L21_T3_34_N") (class "Default")
      (node (ref "J1") (pin "76") (pinfunction "76_76") (pintype "passive"))
      (node (ref "J16") (pin "63") (pinfunction "63_63") (pintype "passive"))
    )
    (net (code "105") (name "/L21_T3_34_P") (class "Default")
      (node (ref "J1") (pin "74") (pinfunction "74_74") (pintype "passive"))
      (node (ref "J16") (pin "61") (pinfunction "61_61") (pintype "passive"))
    )
    (net (code "106") (name "/L21_T3_35_N") (class "Default")
      (node (ref "J17") (pin "65") (pinfunction "65_65") (pintype "passive"))
      (node (ref "J2") (pin "84") (pinfunction "84_84") (pintype "passive"))
    )
    (net (code "107") (name "/L21_T3_35_P") (class "Default")
      (node (ref "J17") (pin "63") (pinfunction "63_63") (pintype "passive"))
      (node (ref "J2") (pin "82") (pinfunction "82_82") (pintype "passive"))
    )
    (net (code "108") (name "/L22_T3_13_N") (class "Default")
      (node (ref "J17") (pin "76") (pinfunction "76_76") (pintype "passive"))
      (node (ref "J2") (pin "99") (pinfunction "99_99") (pintype "passive"))
    )
    (net (code "109") (name "/L22_T3_13_P") (class "Default")
      (node (ref "J17") (pin "74") (pinfunction "74_74") (pintype "passive"))
      (node (ref "J2") (pin "97") (pinfunction "97_97") (pintype "passive"))
    )
    (net (code "110") (name "/L22_T3_34_N") (class "Default")
      (node (ref "J1") (pin "83") (pinfunction "83_83") (pintype "passive"))
      (node (ref "J16") (pin "68") (pinfunction "68_68") (pintype "passive"))
    )
    (net (code "111") (name "/L22_T3_34_P") (class "Default")
      (node (ref "J1") (pin "81") (pinfunction "81_81") (pintype "passive"))
      (node (ref "J16") (pin "66") (pinfunction "66_66") (pintype "passive"))
    )
    (net (code "112") (name "/L22_T3_35_N") (class "Default")
      (node (ref "J17") (pin "66") (pinfunction "66_66") (pintype "passive"))
      (node (ref "J2") (pin "89") (pinfunction "89_89") (pintype "passive"))
    )
    (net (code "113") (name "/L22_T3_35_P") (class "Default")
      (node (ref "J17") (pin "64") (pinfunction "64_64") (pintype "passive"))
      (node (ref "J2") (pin "87") (pinfunction "87_87") (pintype "passive"))
    )
    (net (code "114") (name "/L23_T3_34_N") (class "Default")
      (node (ref "J1") (pin "84") (pinfunction "84_84") (pintype "passive"))
      (node (ref "J16") (pin "67") (pinfunction "67_67") (pintype "passive"))
    )
    (net (code "115") (name "/L23_T3_34_P") (class "Default")
      (node (ref "J1") (pin "82") (pinfunction "82_82") (pintype "passive"))
      (node (ref "J16") (pin "65") (pinfunction "65_65") (pintype "passive"))
    )
    (net (code "116") (name "/L23_T3_35_N") (class "Default")
      (node (ref "J17") (pin "71") (pinfunction "71_71") (pintype "passive"))
      (node (ref "J2") (pin "90") (pinfunction "90_90") (pintype "passive"))
    )
    (net (code "117") (name "/L23_T3_35_P") (class "Default")
      (node (ref "J17") (pin "69") (pinfunction "69_69") (pintype "passive"))
      (node (ref "J2") (pin "88") (pinfunction "88_88") (pintype "passive"))
    )
    (net (code "118") (name "/PG_1V8") (class "Default")
      (node (ref "J2") (pin "10") (pinfunction "10_10") (pintype "passive"))
      (node (ref "R14") (pin "2") (pinfunction "2_2") (pintype "passive"))
    )
    (net (code "119") (name "/PG_CARRIER") (class "Default")
      (node (ref "J2") (pin "11") (pinfunction "11_11") (pintype "passive"))
    )
    (net (code "120") (name "/PWR_EN") (class "Default")
      (node (ref "J1") (pin "5") (pinfunction "5_5") (pintype "passive"))
      (node (ref "Q1") (pin "3") (pinfunction "D_3") (pintype "passive"))
    )
    (net (code "121") (name "/REG_EN") (class "Default")
      (node (ref "R13") (pin "2") (pinfunction "2_2") (pintype "passive"))
      (node (ref "R14") (pin "1") (pinfunction "1_1") (pintype "passive"))
      (node (ref "U1") (pin "1") (pinfunction "EN_1") (pintype "input"))
      (node (ref "U2") (pin "1") (pinfunction "EN_1") (pintype "input"))
      (node (ref "U3") (pin "1") (pinfunction "EN_1") (pintype "input"))
    )
    (net (code "122") (name "GND") (class "Default")
      (node (ref "C1") (pin "2") (pintype "passive"))
      (node (ref "C10") (pin "1") (pintype "passive"))
      (node (ref "C11") (pin "1") (pintype "passive"))
      (node (ref "C12") (pin "2") (pintype "passive"))
      (node (ref "C16") (pin "1") (pintype "passive"))
      (node (ref "C17") (pin "1") (pintype "passive"))
      (node (ref "C18") (pin "1") (pintype "passive"))
      (node (ref "C19") (pin "1") (pintype "passive"))
      (node (ref "C2") (pin "1") (pintype "passive"))
      (node (ref "C20") (pin "1") (pintype "passive"))
      (node (ref "C21") (pin "1") (pintype "passive"))
      (node (ref "C22") (pin "1") (pintype "passive"))
      (node (ref "C24") (pin "1") (pintype "passive"))
      (node (ref "C25") (pin "1") (pintype "passive"))
      (node (ref "C3") (pin "1") (pintype "passive"))
      (node (ref "C4") (pin "2") (pintype "passive"))
      (node (ref "C5") (pin "2") (pintype "passive"))
      (node (ref "C6") (pin "1") (pintype "passive"))
      (node (ref "C7") (pin "1") (pintype "passive"))
      (node (ref "C8") (pin "2") (pintype "passive"))
      (node (ref "C9") (pin "2") (pintype "passive"))
      (node (ref "J1") (pin "100") (pinfunction "100_100") (pintype "passive"))
      (node (ref "J1") (pin "15") (pinfunction "15_15") (pintype "passive"))
      (node (ref "J1") (pin "16") (pinfunction "16_16") (pintype "passive"))
      (node (ref "J1") (pin "21") (pinfunction "21_21") (pintype "passive"))
      (node (ref "J1") (pin "22") (pinfunction "22_22") (pintype "passive"))
      (node (ref "J1") (pin "27") (pinfunction "27_27") (pintype "passive"))
      (node (ref "J1") (pin "28") (pinfunction "28_28") (pintype "passive"))
      (node (ref "J1") (pin "33") (pinfunction "33_33") (pintype "passive"))
      (node (ref "J1") (pin "34") (pinfunction "34_34") (pintype "passive"))
      (node (ref "J1") (pin "39") (pinfunction "39_39") (pintype "passive"))
      (node (ref "J1") (pin "40") (pinfunction "40_40") (pintype "passive"))
      (node (ref "J1") (pin "45") (pinfunction "45_45") (pintype "passive"))
      (node (ref "J1") (pin "46") (pinfunction "46_46") (pintype "passive"))
      (node (ref "J1") (pin "51") (pinfunction "51_51") (pintype "passive"))
      (node (ref "J1") (pin "52") (pinfunction "52_52") (pintype "passive"))
      (node (ref "J1") (pin "65") (pinfunction "65_65") (pintype "passive"))
      (node (ref "J1") (pin "66") (pinfunction "66_66") (pintype "passive"))
      (node (ref "J1") (pin "71") (pinfunction "71_71") (pintype "passive"))
      (node (ref "J1") (pin "72") (pinfunction "72_72") (pintype "passive"))
      (node (ref "J1") (pin "77") (pinfunction "77_77") (pintype "passive"))
      (node (ref "J1") (pin "85") (pinfunction "85_85") (pintype "passive"))
      (node (ref "J1") (pin "86") (pinfunction "86_86") (pintype "passive"))
      (node (ref "J1") (pin "95") (pinfunction "95_95") (pintype "passive"))
      (node (ref "J1") (pin "96") (pinfunction "96_96") (pintype "passive"))
      (node (ref "J1") (pin "97") (pinfunction "97_97") (pintype "passive"))
      (node (ref "J1") (pin "98") (pinfunction "98_98") (pintype "passive"))
      (node (ref "J1") (pin "99") (pinfunction "99_99") (pintype "passive"))
      (node (ref "J12") (pin "5") (pinfunction "GND_5") (pintype "power_in"))
      (node (ref "J12") (pin "6") (pinfunction "S1_6") (pintype "passive"))
      (node (ref "J12") (pin "7") (pinfunction "S2_7") (pintype "power_in"))
      (node (ref "J12") (pin "8") (pinfunction "S3_8") (pintype "power_in"))
      (node (ref "J12") (pin "9") (pinfunction "S4_9") (pintype "power_in"))
      (node (ref "J16") (pin "1") (pinfunction "1_1") (pintype "passive"))
      (node (ref "J16") (pin "13") (pinfunction "13_13") (pintype "passive"))
      (node (ref "J16") (pin "14") (pinfunction "14_14") (pintype "passive"))
      (node (ref "J16") (pin "2") (pinfunction "2_2") (pintype "passive"))
      (node (ref "J16") (pin "23") (pinfunction "23_23") (pintype "passive"))
      (node (ref "J16") (pin "24") (pinfunction "24_24") (pintype "passive"))
      (node (ref "J16") (pin "29") (pinfunction "29_29") (pintype "passive"))
      (node (ref "J16") (pin "30") (pinfunction "30_30") (pintype "passive"))
      (node (ref "J16") (pin "35") (pinfunction "35_35") (pintype "passive"))
      (node (ref "J16") (pin "36") (pinfunction "36_36") (pintype "passive"))
      (node (ref "J16") (pin "41") (pinfunction "41_41") (pintype "passive"))
      (node (ref "J16") (pin "42") (pinfunction "42_42") (pintype "passive"))
      (node (ref "J16") (pin "47") (pinfunction "47_47") (pintype "passive"))
      (node (ref "J16") (pin "48") (pinfunction "48_48") (pintype "passive"))
      (node (ref "J16") (pin "53") (pinfunction "53_53") (pintype "passive"))
      (node (ref "J16") (pin "54") (pinfunction "54_54") (pintype "passive"))
      (node (ref "J16") (pin "59") (pinfunction "59_59") (pintype "passive"))
      (node (ref "J16") (pin "60") (pinfunction "60_60") (pintype "passive"))
      (node (ref "J16") (pin "69") (pinfunction "69_69") (pintype "passive"))
      (node (ref "J16") (pin "70") (pinfunction "70_70") (pintype "passive"))
      (node (ref "J16") (pin "79") (pinfunction "79_79") (pintype "passive"))
      (node (ref "J16") (pin "80") (pinfunction "80_80") (pintype "passive"))
      (node (ref "J17") (pin "11") (pinfunction "11_11") (pintype "passive"))
      (node (ref "J17") (pin "12") (pinfunction "12_12") (pintype "passive"))
      (node (ref "J17") (pin "21") (pinfunction "21_21") (pintype "passive"))
      (node (ref "J17") (pin "22") (pinfunction "22_22") (pintype "passive"))
      (node (ref "J17") (pin "27") (pinfunction "27_27") (pintype "passive"))
      (node (ref "J17") (pin "28") (pinfunction "28_28") (pintype "passive"))
      (node (ref "J17") (pin "33") (pinfunction "33_33") (pintype "passive"))
      (node (ref "J17") (pin "34") (pinfunction "34_34") (pintype "passive"))
      (node (ref "J17") (pin "39") (pinfunction "39_39") (pintype "passive"))
      (node (ref "J17") (pin "40") (pinfunction "40_40") (pintype "passive"))
      (node (ref "J17") (pin "45") (pinfunction "45_45") (pintype "passive"))
      (node (ref "J17") (pin "46") (pinfunction "46_46") (pintype "passive"))
      (node (ref "J17") (pin "51") (pinfunction "51_51") (pintype "passive"))
      (node (ref "J17") (pin "52") (pinfunction "52_52") (pintype "passive"))
      (node (ref "J17") (pin "57") (pinfunction "57_57") (pintype "passive"))
      (node (ref "J17") (pin "58") (pinfunction "58_58") (pintype "passive"))
      (node (ref "J17") (pin "67") (pinfunction "67_67") (pintype "passive"))
      (node (ref "J17") (pin "68") (pinfunction "68_68") (pintype "passive"))
      (node (ref "J17") (pin "77") (pinfunction "77_77") (pintype "passive"))
      (node (ref "J17") (pin "79") (pinfunction "79_79") (pintype "passive"))
      (node (ref "J17") (pin "80") (pinfunction "80_80") (pintype "passive"))
      (node (ref "J19") (pin "1") (pinfunction "PW_1") (pintype "passive"))
      (node (ref "J2") (pin "15") (pinfunction "15_15") (pintype "passive"))
      (node (ref "J2") (pin "16") (pinfunction "16_16") (pintype "passive"))
      (node (ref "J2") (pin "21") (pinfunction "21_21") (pintype "passive"))
      (node (ref "J2") (pin "22") (pinfunction "22_22") (pintype "passive"))
      (node (ref "J2") (pin "27") (pinfunction "27_27") (pintype "passive"))
      (node (ref "J2") (pin "28") (pinfunction "28_28") (pintype "passive"))
      (node (ref "J2") (pin "33") (pinfunction "33_33") (pintype "passive"))
      (node (ref "J2") (pin "34") (pinfunction "34_34") (pintype "passive"))
      (node (ref "J2") (pin "39") (pinfunction "39_39") (pintype "passive"))
      (node (ref "J2") (pin "40") (pinfunction "40_40") (pintype "passive"))
      (node (ref "J2") (pin "45") (pinfunction "45_45") (pintype "passive"))
      (node (ref "J2") (pin "46") (pinfunction "46_46") (pintype "passive"))
      (node (ref "J2") (pin "51") (pinfunction "51_51") (pintype "passive"))
      (node (ref "J2") (pin "52") (pinfunction "52_52") (pintype "passive"))
      (node (ref "J2") (pin "65") (pinfunction "65_65") (pintype "passive"))
      (node (ref "J2") (pin "66") (pinfunction "66_66") (pintype "passive"))
      (node (ref "J2") (pin "71") (pinfunction "71_71") (pintype "passive"))
      (node (ref "J2") (pin "72") (pinfunction "72_72") (pintype "passive"))
      (node (ref "J2") (pin "77") (pinfunction "77_77") (pintype "passive"))
      (node (ref "J2") (pin "85") (pinfunction "85_85") (pintype "passive"))
      (node (ref "J2") (pin "86") (pinfunction "86_86") (pintype "passive"))
      (node (ref "J2") (pin "91") (pinfunction "91_91") (pintype "passive"))
      (node (ref "J2") (pin "92") (pinfunction "92_92") (pintype "passive"))
      (node (ref "Q1") (pin "2") (pinfunction "S_2") (pintype "passive"))
      (node (ref "R12") (pin "2") (pinfunction "2_2") (pintype "passive"))
      (node (ref "R16") (pin "2") (pinfunction "2_2") (pintype "passive"))
      (node (ref "R4") (pin "2") (pinfunction "2_2") (pintype "passive"))
      (node (ref "R8") (pin "1") (pinfunction "1_1") (pintype "passive"))
      (node (ref "U1") (pin "2") (pinfunction "GND_2") (pintype "power_in"))
      (node (ref "U2") (pin "2") (pinfunction "GND_2") (pintype "power_in"))
      (node (ref "U3") (pin "2") (pinfunction "GND_2") (pintype "power_in"))
    )
    (net (code "123") (name "Net-(J3-Pad2)") (class "Default")
      (node (ref "J3") (pin "2") (pinfunction "2_2") (pintype "passive"))
      (node (ref "R1") (pin "1") (pinfunction "1_1") (pintype "passive"))
    )
    (net (code "124") (name "Net-(J4-Pad2)") (class "Default")
      (node (ref "J4") (pin "2") (pinfunction "2_2") (pintype "passive"))
      (node (ref "R2") (pin "1") (pinfunction "1_1") (pintype "passive"))
    )
    (net (code "125") (name "Net-(J5-Pad2)") (class "Default")
      (node (ref "J5") (pin "2") (pinfunction "2_2") (pintype "passive"))
      (node (ref "R3") (pin "1") (pinfunction "1_1") (pintype "passive"))
    )
    (net (code "126") (name "Net-(J6-Pad2)") (class "Default")
      (node (ref "J6") (pin "2") (pinfunction "2_2") (pintype "passive"))
      (node (ref "R5") (pin "2") (pinfunction "2_2") (pintype "passive"))
    )
    (net (code "127") (name "Net-(J7-Pad2)") (class "Default")
      (node (ref "J7") (pin "2") (pinfunction "2_2") (pintype "passive"))
      (node (ref "R6") (pin "2") (pinfunction "2_2") (pintype "passive"))
    )
    (net (code "128") (name "Net-(J8-Pad2)") (class "Default")
      (node (ref "J8") (pin "2") (pinfunction "2_2") (pintype "passive"))
      (node (ref "R7") (pin "2") (pinfunction "2_2") (pintype "passive"))
    )
    (net (code "129") (name "Net-(J9-Pad2)") (class "Default")
      (node (ref "J9") (pin "2") (pinfunction "2_2") (pintype "passive"))
      (node (ref "R9") (pin "1") (pinfunction "1_1") (pintype "passive"))
    )
    (net (code "130") (name "Net-(J10-Pad2)") (class "Default")
      (node (ref "J10") (pin "2") (pinfunction "2_2") (pintype "passive"))
      (node (ref "R10") (pin "1") (pinfunction "1_1") (pintype "passive"))
    )
    (net (code "131") (name "Net-(J11-Pad2)") (class "Default")
      (node (ref "J11") (pin "2") (pinfunction "2_2") (pintype "passive"))
      (node (ref "R11") (pin "1") (pinfunction "1_1") (pintype "passive"))
    )
    (net (code "132") (name "Net-(Q1-G)") (class "Default")
      (node (ref "Q1") (pin "1") (pinfunction "G_1") (pintype "passive"))
      (node (ref "R15") (pin "1") (pinfunction "1_1") (pintype "passive"))
      (node (ref "R16") (pin "1") (pinfunction "1_1") (pintype "passive"))
    )
    (net (code "133") (name "Net-(SW1-P1)") (class "Default")
      (node (ref "R15") (pin "2") (pinfunction "2_2") (pintype "passive"))
      (node (ref "SW1") (pin "1") (pinfunction "P1_1") (pintype "passive"))
    )
    (net (code "134") (name "Net-(U1-FB)") (class "Default")
      (node (ref "R1") (pin "2") (pinfunction "2_2") (pintype "passive"))
      (node (ref "R2") (pin "2") (pinfunction "2_2") (pintype "passive"))
      (node (ref "R3") (pin "2") (pinfunction "2_2") (pintype "passive"))
      (node (ref "R4") (pin "1") (pinfunction "1_1") (pintype "passive"))
      (node (ref "U1") (pin "5") (pinfunction "FB_5") (pintype "input"))
    )
    (net (code "135") (name "Net-(U1-LX)") (class "Default")
      (node (ref "L1") (pin "1") (pinfunction "1_1") (pintype "passive"))
      (node (ref "U1") (pin "3") (pinfunction "LX_3") (pintype "passive"))
    )
    (net (code "136") (name "Net-(U2-FB)") (class "Default")
      (node (ref "R5") (pin "1") (pinfunction "1_1") (pintype "passive"))
      (node (ref "R6") (pin "1") (pinfunction "1_1") (pintype "passive"))
      (node (ref "R7") (pin "1") (pinfunction "1_1") (pintype "passive"))
      (node (ref "R8") (pin "2") (pinfunction "2_2") (pintype "passive"))
      (node (ref "U2") (pin "5") (pinfunction "FB_5") (pintype "input"))
    )
    (net (code "137") (name "Net-(U2-LX)") (class "Default")
      (node (ref "L2") (pin "1") (pinfunction "1_1") (pintype "passive"))
      (node (ref "U2") (pin "3") (pinfunction "LX_3") (pintype "passive"))
    )
    (net (code "138") (name "Net-(U3-FB)") (class "Default")
      (node (ref "R10") (pin "2") (pinfunction "2_2") (pintype "passive"))
      (node (ref "R11") (pin "2") (pinfunction "2_2") (pintype "passive"))
      (node (ref "R12") (pin "1") (pinfunction "1_1") (pintype "passive"))
      (node (ref "R9") (pin "2") (pinfunction "2_2") (pintype "passive"))
      (node (ref "U3") (pin "5") (pinfunction "FB_5") (pintype "input"))
    )
    (net (code "139") (name "Net-(U3-LX)") (class "Default")
      (node (ref "L3") (pin "1") (pinfunction "1_1") (pintype "passive"))
      (node (ref "U3") (pin "3") (pinfunction "LX_3") (pintype "passive"))
    )
    (net (code "140") (name "VCCIO_13") (class "Default")
      (node (ref "C24") (pin "2") (pintype "passive"))
      (node (ref "C25") (pin "2") (pintype "passive"))
      (node (ref "C7") (pin "2") (pintype "passive"))
      (node (ref "C8") (pin "1") (pintype "passive"))
      (node (ref "J13") (pin "2") (pinfunction "2_2") (pintype "passive"))
      (node (ref "J14") (pin "2") (pinfunction "2_2") (pintype "passive"))
      (node (ref "J2") (pin "98") (pinfunction "98_98") (pintype "passive"))
      (node (ref "J6") (pin "1") (pinfunction "1_1") (pintype "passive"))
      (node (ref "J7") (pin "1") (pinfunction "1_1") (pintype "passive"))
      (node (ref "J8") (pin "1") (pinfunction "1_1") (pintype "passive"))
      (node (ref "L2") (pin "2") (pinfunction "2_2") (pintype "passive"))
    )
    (net (code "141") (name "VCCIO_34") (class "Default")
      (node (ref "C11") (pin "2") (pintype "passive"))
      (node (ref "C12") (pin "1") (pintype "passive"))
      (node (ref "C16") (pin "2") (pintype "passive"))
      (node (ref "C17") (pin "2") (pintype "passive"))
      (node (ref "C18") (pin "2") (pintype "passive"))
      (node (ref "C19") (pin "2") (pintype "passive"))
      (node (ref "J1") (pin "78") (pinfunction "78_78") (pintype "passive"))
      (node (ref "J1") (pin "79") (pinfunction "79_79") (pintype "passive"))
      (node (ref "J1") (pin "80") (pinfunction "80_80") (pintype "passive"))
      (node (ref "J10") (pin "1") (pinfunction "1_1") (pintype "passive"))
      (node (ref "J11") (pin "1") (pinfunction "1_1") (pintype "passive"))
      (node (ref "J13") (pin "1") (pinfunction "1_1") (pintype "passive"))
      (node (ref "J15") (pin "1") (pinfunction "1_1") (pintype "passive"))
      (node (ref "J9") (pin "1") (pinfunction "1_1") (pintype "passive"))
      (node (ref "L3") (pin "2") (pinfunction "2_2") (pintype "passive"))
    )
    (net (code "142") (name "VCCIO_35") (class "Default")
      (node (ref "C20") (pin "2") (pintype "passive"))
      (node (ref "C21") (pin "2") (pintype "passive"))
      (node (ref "C22") (pin "2") (pintype "passive"))
      (node (ref "C3") (pin "2") (pintype "passive"))
      (node (ref "C4") (pin "1") (pintype "passive"))
      (node (ref "J14") (pin "1") (pinfunction "1_1") (pintype "passive"))
      (node (ref "J15") (pin "2") (pinfunction "2_2") (pintype "passive"))
      (node (ref "J2") (pin "78") (pinfunction "78_78") (pintype "passive"))
      (node (ref "J2") (pin "79") (pinfunction "79_79") (pintype "passive"))
      (node (ref "J2") (pin "80") (pinfunction "80_80") (pintype "passive"))
      (node (ref "J3") (pin "1") (pinfunction "1_1") (pintype "passive"))
      (node (ref "J4") (pin "1") (pinfunction "1_1") (pintype "passive"))
      (node (ref "J5") (pin "1") (pinfunction "1_1") (pintype "passive"))
      (node (ref "L1") (pin "2") (pinfunction "2_2") (pintype "passive"))
    )
    (net (code "143") (name "unconnected-(J1-Pad1)") (class "Default")
      (node (ref "J1") (pin "1") (pinfunction "1_1") (pintype "passive"))
    )
    (net (code "144") (name "unconnected-(J1-Pad2)") (class "Default")
      (node (ref "J1") (pin "2") (pinfunction "2_2") (pintype "passive"))
    )
    (net (code "145") (name "unconnected-(J1-Pad3)") (class "Default")
      (node (ref "J1") (pin "3") (pinfunction "3_3") (pintype "passive"))
    )
    (net (code "146") (name "unconnected-(J1-Pad4)") (class "Default")
      (node (ref "J1") (pin "4") (pinfunction "4_4") (pintype "passive"))
    )
    (net (code "147") (name "unconnected-(J1-Pad6)") (class "Default")
      (node (ref "J1") (pin "6") (pinfunction "6_6") (pintype "passive"))
    )
    (net (code "148") (name "unconnected-(J1-Pad7)") (class "Default")
      (node (ref "J1") (pin "7") (pinfunction "7_7") (pintype "passive"))
    )
    (net (code "149") (name "unconnected-(J1-Pad8)") (class "Default")
      (node (ref "J1") (pin "8") (pinfunction "8_8") (pintype "passive"))
    )
    (net (code "150") (name "unconnected-(J2-Pad1)") (class "Default")
      (node (ref "J2") (pin "1") (pinfunction "1_1") (pintype "passive"))
    )
    (net (code "151") (name "unconnected-(J2-Pad2)") (class "Default")
      (node (ref "J2") (pin "2") (pinfunction "2_2") (pintype "passive"))
    )
    (net (code "152") (name "unconnected-(J2-Pad3)") (class "Default")
      (node (ref "J2") (pin "3") (pinfunction "3_3") (pintype "passive"))
    )
    (net (code "153") (name "unconnected-(J2-Pad4)") (class "Default")
      (node (ref "J2") (pin "4") (pinfunction "4_4") (pintype "passive"))
    )
    (net (code "154") (name "unconnected-(J2-Pad5)") (class "Default")
      (node (ref "J2") (pin "5") (pinfunction "5_5") (pintype "passive"))
    )
    (net (code "155") (name "unconnected-(J2-Pad6)") (class "Default")
      (node (ref "J2") (pin "6") (pinfunction "6_6") (pintype "passive"))
    )
    (net (code "156") (name "unconnected-(J2-Pad7)") (class "Default")
      (node (ref "J2") (pin "7") (pinfunction "7_7") (pintype "passive"))
    )
    (net (code "157") (name "unconnected-(J2-Pad8)") (class "Default")
      (node (ref "J2") (pin "8") (pinfunction "8_8") (pintype "passive"))
    )
    (net (code "158") (name "unconnected-(J2-Pad9)") (class "Default")
      (node (ref "J2") (pin "9") (pinfunction "9_9") (pintype "passive"))
    )
    (net (code "159") (name "unconnected-(J12-D+-Pad3)") (class "Default")
      (node (ref "J12") (pin "3") (pinfunction "D+_3") (pintype "bidirectional"))
    )
    (net (code "160") (name "unconnected-(J12-D--Pad2)") (class "Default")
      (node (ref "J12") (pin "2") (pinfunction "D-_2") (pintype "bidirectional"))
    )
    (net (code "161") (name "unconnected-(J12-ID-Pad4)") (class "Default")
      (node (ref "J12") (pin "4") (pinfunction "ID_4") (pintype "passive"))
    )
  )
)
